# Proiect-TSC_v16.net
KiCad netlist of a schematic drawn in EAGLE
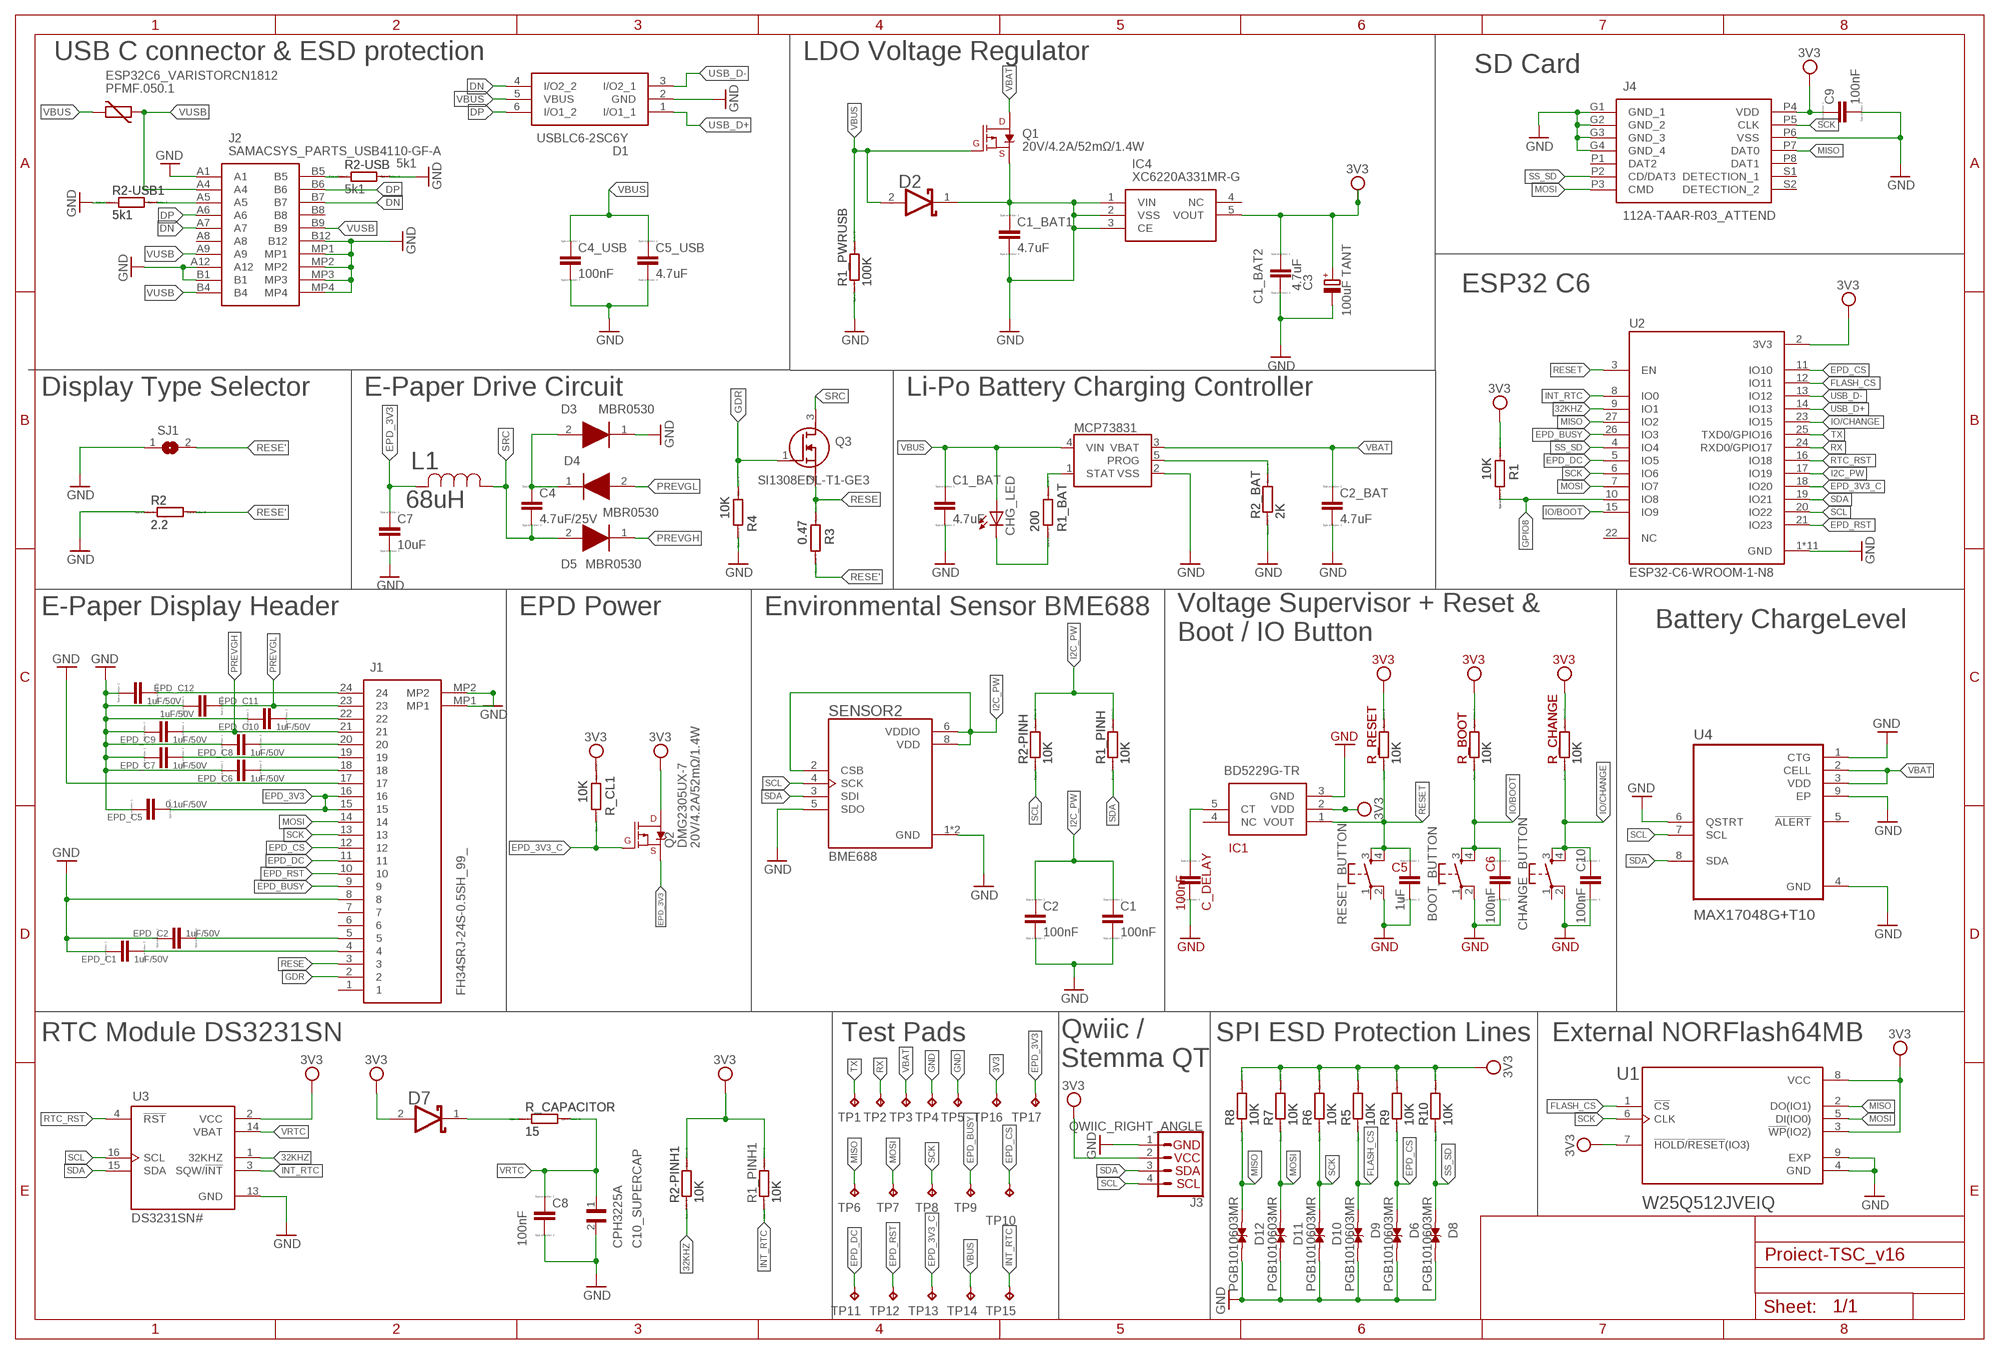
[diagram p0: schematic, sheet 1]

(export (version "E")
  (design (tool "Eeschema 10.0.6"))
  (components
    (comp (ref "BOOT_BUTTON")
      (value "BUTTON_CUSYOMV1")
      (footprint "eagle-import:MYBUTTON")
      (libsource (lib "eagle-import") (part "BUTTON_CUSYOMV1"))
    )
    (comp (ref "C1")
      (value "100nF")
      (footprint "eagle-import:EAGLE-LTSPICE_C0402")
      (libsource (lib "eagle-import") (part "EAGLE-LTSPICE_CC0402"))
    )
    (comp (ref "C1_BAT")
      (value "4.7uF")
      (footprint "eagle-import:EAGLE-LTSPICE_C0402")
      (libsource (lib "eagle-import") (part "EAGLE-LTSPICE_CC0402"))
    )
    (comp (ref "C1_BAT1")
      (value "4.7uF")
      (footprint "eagle-import:EAGLE-LTSPICE_C0402")
      (libsource (lib "eagle-import") (part "EAGLE-LTSPICE_CC0402"))
    )
    (comp (ref "C1_BAT2")
      (value "4.7uF")
      (footprint "eagle-import:EAGLE-LTSPICE_C0402")
      (libsource (lib "eagle-import") (part "EAGLE-LTSPICE_CC0402"))
    )
    (comp (ref "C2")
      (value "100nF")
      (footprint "eagle-import:EAGLE-LTSPICE_C0402")
      (libsource (lib "eagle-import") (part "EAGLE-LTSPICE_CC0402"))
    )
    (comp (ref "C2_BAT")
      (value "4.7uF")
      (footprint "eagle-import:EAGLE-LTSPICE_C0402")
      (libsource (lib "eagle-import") (part "EAGLE-LTSPICE_CC0402"))
    )
    (comp (ref "C3")
      (value "100uF TANT")
      (footprint "eagle-import:RCL_CT3528")
      (libsource (lib "eagle-import") (part "RCL_CPOL-EUCT3528"))
    )
    (comp (ref "C4")
      (value "4.7uF/25V")
      (footprint "eagle-import:EAGLE-LTSPICE_C0402")
      (libsource (lib "eagle-import") (part "EAGLE-LTSPICE_CC0402"))
    )
    (comp (ref "C4_USB")
      (value "100nF")
      (footprint "eagle-import:EAGLE-LTSPICE_C0402")
      (libsource (lib "eagle-import") (part "EAGLE-LTSPICE_CC0402"))
    )
    (comp (ref "C5")
      (value "1uF")
      (footprint "eagle-import:EAGLE-LTSPICE_C0402")
      (libsource (lib "eagle-import") (part "EAGLE-LTSPICE_CC0402"))
    )
    (comp (ref "C5_USB")
      (value "4.7uF")
      (footprint "eagle-import:EAGLE-LTSPICE_C0402")
      (libsource (lib "eagle-import") (part "EAGLE-LTSPICE_CC0402"))
    )
    (comp (ref "C6")
      (value "100nF")
      (footprint "eagle-import:EAGLE-LTSPICE_C0402")
      (libsource (lib "eagle-import") (part "EAGLE-LTSPICE_CC0402"))
    )
    (comp (ref "C7")
      (value "10uF")
      (footprint "eagle-import:EAGLE-LTSPICE_C0402")
      (libsource (lib "eagle-import") (part "EAGLE-LTSPICE_CC0402"))
    )
    (comp (ref "C8")
      (value "100nF")
      (footprint "eagle-import:EAGLE-LTSPICE_C0402")
      (libsource (lib "eagle-import") (part "EAGLE-LTSPICE_CC0402"))
    )
    (comp (ref "C9")
      (value "100nF")
      (footprint "eagle-import:EAGLE-LTSPICE_C0402")
      (libsource (lib "eagle-import") (part "EAGLE-LTSPICE_CC0402"))
    )
    (comp (ref "C10")
      (value "100nF")
      (footprint "eagle-import:EAGLE-LTSPICE_C0402")
      (libsource (lib "eagle-import") (part "EAGLE-LTSPICE_CC0402"))
    )
    (comp (ref "C10_SUPERCAP")
      (value "CPH3225A")
      (footprint "eagle-import:CAPCP3225X100N")
      (fields (field (name "MF") "Seiko Instruments"))
      (libsource (lib "eagle-import") (part "CPH3225A"))
    )
    (comp (ref "CHANGE_BUTTON")
      (value "BUTTON_CUSYOMV1")
      (footprint "eagle-import:MYBUTTON")
      (libsource (lib "eagle-import") (part "BUTTON_CUSYOMV1"))
    )
    (comp (ref "CHG_LED")
      (value "1")
      (footprint "eagle-import:ADAFRUIT_CHIP-LED0603")
      (libsource (lib "eagle-import") (part "ADAFRUIT_LEDCHIP-LED0603"))
    )
    (comp (ref "C_DELAY")
      (value "100nF")
      (footprint "eagle-import:EAGLE-LTSPICE_C0402")
      (libsource (lib "eagle-import") (part "EAGLE-LTSPICE_CC0402"))
    )
    (comp (ref "D1")
      (value "USBLC6-2SC6Y")
      (footprint "eagle-import:SOT95P280X145-6N")
      (fields (field (name "MF") "STMicroelectronics"))
      (libsource (lib "eagle-import") (part "USBLC6-2SC6Y"))
    )
    (comp (ref "D2")
      (value "ESP32_WROVER_AVX---SD0805S020S1R0_AVX_SD0805S020S1R0_0_0AVX_SD0805S020S1R0_0_0")
      (footprint "eagle-import:ESP32_WROVER_AVX---SD0805S020S1R0_AVX_SD0805S020S1R0_0")
      (fields
        (field (name "DIGIKEY_PART_NUMBER") "478-7800-1-ND")
        (field (name "MF") "AVX")
        (field (name "MOUSER_PART_NUMBER") "581-SD0805S020S1R0")
      )
      (libsource (lib "eagle-import") (part "ESP32_WROVER_AVX---SD0805S020S1R0_AVX_SD0805S020S1R0_0_0AVX_SD0805S020S1R0_0_0"))
    )
    (comp (ref "D3")
      (value "MBR0530")
      (footprint "eagle-import:SOD3716X135N")
      (fields (field (name "MF") "ON Semiconductor"))
      (libsource (lib "eagle-import") (part "MBR0530"))
    )
    (comp (ref "D4")
      (value "MBR0530")
      (footprint "eagle-import:SOD3716X135N")
      (fields (field (name "MF") "ON Semiconductor"))
      (libsource (lib "eagle-import") (part "MBR0530"))
    )
    (comp (ref "D5")
      (value "MBR0530")
      (footprint "eagle-import:SOD3716X135N")
      (fields (field (name "MF") "ON Semiconductor"))
      (libsource (lib "eagle-import") (part "MBR0530"))
    )
    (comp (ref "D6")
      (value "PGB1010603MR")
      (footprint "eagle-import:DIOC1608X36N")
      (fields (field (name "MF") "Littelfuse Inc."))
      (libsource (lib "eagle-import") (part "PGB1010603MR"))
    )
    (comp (ref "D7")
      (value "ESP32_WROVER_AVX---SD0805S020S1R0_AVX_SD0805S020S1R0_0_0AVX_SD0805S020S1R0_0_0")
      (footprint "eagle-import:ESP32_WROVER_AVX---SD0805S020S1R0_AVX_SD0805S020S1R0_0")
      (fields
        (field (name "DIGIKEY_PART_NUMBER") "478-7800-1-ND")
        (field (name "MF") "AVX")
        (field (name "MOUSER_PART_NUMBER") "581-SD0805S020S1R0")
      )
      (libsource (lib "eagle-import") (part "ESP32_WROVER_AVX---SD0805S020S1R0_AVX_SD0805S020S1R0_0_0AVX_SD0805S020S1R0_0_0"))
    )
    (comp (ref "D8")
      (value "PGB1010603MR")
      (footprint "eagle-import:DIOC1608X36N")
      (fields (field (name "MF") "Littelfuse Inc."))
      (libsource (lib "eagle-import") (part "PGB1010603MR"))
    )
    (comp (ref "D9")
      (value "PGB1010603MR")
      (footprint "eagle-import:DIOC1608X36N")
      (fields (field (name "MF") "Littelfuse Inc."))
      (libsource (lib "eagle-import") (part "PGB1010603MR"))
    )
    (comp (ref "D10")
      (value "PGB1010603MR")
      (footprint "eagle-import:DIOC1608X36N")
      (fields (field (name "MF") "Littelfuse Inc."))
      (libsource (lib "eagle-import") (part "PGB1010603MR"))
    )
    (comp (ref "D11")
      (value "PGB1010603MR")
      (footprint "eagle-import:DIOC1608X36N")
      (fields (field (name "MF") "Littelfuse Inc."))
      (libsource (lib "eagle-import") (part "PGB1010603MR"))
    )
    (comp (ref "D12")
      (value "PGB1010603MR")
      (footprint "eagle-import:DIOC1608X36N")
      (fields (field (name "MF") "Littelfuse Inc."))
      (libsource (lib "eagle-import") (part "PGB1010603MR"))
    )
    (comp (ref "EPD_C1")
      (value "1uF/50V")
      (footprint "eagle-import:EAGLE-LTSPICE_C0402")
      (libsource (lib "eagle-import") (part "EAGLE-LTSPICE_CC0402"))
    )
    (comp (ref "EPD_C2")
      (value "1uF/50V")
      (footprint "eagle-import:EAGLE-LTSPICE_C0402")
      (libsource (lib "eagle-import") (part "EAGLE-LTSPICE_CC0402"))
    )
    (comp (ref "EPD_C5")
      (value "0.1uF/50V")
      (footprint "eagle-import:EAGLE-LTSPICE_C0402")
      (libsource (lib "eagle-import") (part "EAGLE-LTSPICE_CC0402"))
    )
    (comp (ref "EPD_C6")
      (value "1uF/50V")
      (footprint "eagle-import:EAGLE-LTSPICE_C0402")
      (libsource (lib "eagle-import") (part "EAGLE-LTSPICE_CC0402"))
    )
    (comp (ref "EPD_C7")
      (value "1uF/50V")
      (footprint "eagle-import:EAGLE-LTSPICE_C0402")
      (libsource (lib "eagle-import") (part "EAGLE-LTSPICE_CC0402"))
    )
    (comp (ref "EPD_C8")
      (value "1uF/50V")
      (footprint "eagle-import:EAGLE-LTSPICE_C0402")
      (libsource (lib "eagle-import") (part "EAGLE-LTSPICE_CC0402"))
    )
    (comp (ref "EPD_C9")
      (value "1uF/50V")
      (footprint "eagle-import:EAGLE-LTSPICE_C0402")
      (libsource (lib "eagle-import") (part "EAGLE-LTSPICE_CC0402"))
    )
    (comp (ref "EPD_C10")
      (value "1uF/50V")
      (footprint "eagle-import:EAGLE-LTSPICE_C0402")
      (libsource (lib "eagle-import") (part "EAGLE-LTSPICE_CC0402"))
    )
    (comp (ref "EPD_C11")
      (value "1uF/50V")
      (footprint "eagle-import:EAGLE-LTSPICE_C0402")
      (libsource (lib "eagle-import") (part "EAGLE-LTSPICE_CC0402"))
    )
    (comp (ref "EPD_C12")
      (value "1uF/50V")
      (footprint "eagle-import:EAGLE-LTSPICE_C0402")
      (libsource (lib "eagle-import") (part "EAGLE-LTSPICE_CC0402"))
    )
    (comp (ref "IC1")
      (value "BD5229G-TR")
      (footprint "eagle-import:SOT95P280X125-5N")
      (fields (field (name "MOUSER_PART_NUMBER") "755-BD5229G-TR"))
      (libsource (lib "eagle-import") (part "BD5229G-TR"))
    )
    (comp (ref "IC4")
      (value "XC6220A331MR-G")
      (footprint "eagle-import:SOT95P280X120-5N")
      (fields (field (name "MOUSER_PART_NUMBER") "865-XC6220A331MR-G"))
      (libsource (lib "eagle-import") (part "XC6220A331MR-G"))
    )
    (comp (ref "J1")
      (value "FH34SRJ-24S-0.5SH_99_")
      (footprint "eagle-import:FH34SRJ24S05SH99")
      (fields
        (field (name "MANUFACTURER_PART_NUMBER") "FH34SRJ-24S-0.5SH(99)")
        (field (name "MOUSER_PART_NUMBER") "798-FH34SRJ24S05SH99")
      )
      (libsource (lib "eagle-import") (part "FH34SRJ-24S-0.5SH_99_"))
    )
    (comp (ref "J2")
      (value "SAMACSYS_PARTS_USB4110-GF-A")
      (footprint "eagle-import:SAMACSYS_PARTS_USB4110GFA")
      (fields
        (field (name "MANUFACTURER_PART_NUMBER") "USB4110-GF-A")
        (field (name "MOUSER_PART_NUMBER") "640-USB4110-GF-A")
      )
      (libsource (lib "eagle-import") (part "SAMACSYS_PARTS_USB4110-GF-A"))
    )
    (comp (ref "J3")
      (value "QWIIC_RIGHT_ANGLE")
      (footprint "eagle-import:JST04_1MM_RA")
      (libsource (lib "eagle-import") (part "QWIIC_CONNECTORJS-1MM"))
    )
    (comp (ref "J4")
      (value "112A-TAAR-R03_ATTEND")
      (footprint "eagle-import:112ATAARR03ATTEND")
      (fields (field (name "MANUFACTURER_PART_NUMBER") "112A-TAAR-R03 ATTEND"))
      (libsource (lib "eagle-import") (part "112A-TAAR-R03_ATTEND"))
    )
    (comp (ref "L1")
      (value "68uH")
      (footprint "eagle-import:IND_4828-WE-TPC_WRE")
      (fields
        (field (name "MANUFACTURER_PART_NUMBER") "744043680")
        (field (name "COPYRIGHT") "Copyright (C) 2024 Ultra Librarian. All rights reserved.")
      )
      (libsource (lib "eagle-import") (part "744043680IND_4828-WE-TPC_WRE"))
    )
    (comp (ref "MCP73831")
      (value "ESP32_WROVER_SPARKFUN-IC-POWER_MCP73831")
      (footprint "eagle-import:ESP32_WROVER_SPARKFUN-IC-POWER_SOT23-5")
      (libsource (lib "eagle-import") (part "ESP32_WROVER_SPARKFUN-IC-POWER_MCP73831"))
    )
    (comp (ref "PFMF.050.1")
      (value "ESP32C6_VARISTORCN1812")
      (footprint "eagle-import:ESP32C6_VARISTOR_CT_CN1812")
      (libsource (lib "eagle-import") (part "ESP32C6_VARISTORCN1812"))
    )
    (comp (ref "Q1")
      (value "20V/4.2A/52mΩ/1.4W")
      (footprint "eagle-import:ESP32_WROVER_SPARKFUN-DISCRETESEMI_SOT23-3")
      (libsource (lib "eagle-import") (part "ESP32_WROVER_SPARKFUN-DISCRETESEMI_MOSFET_PCH-DMG2305UX-7"))
    )
    (comp (ref "Q2")
      (value "20V/4.2A/52mΩ/1.4W")
      (footprint "eagle-import:ESP32_WROVER_SPARKFUN-DISCRETESEMI_SOT23-3")
      (libsource (lib "eagle-import") (part "ESP32_WROVER_SPARKFUN-DISCRETESEMI_MOSFET_PCH-DMG2305UX-7"))
    )
    (comp (ref "Q3")
      (value "SI1308EDL-T1-GE3")
      (footprint "eagle-import:SOT65P210X110-3N")
      (fields (field (name "MF") "Vishay Siliconix"))
      (libsource (lib "eagle-import") (part "SI1308EDL-T1-GE3"))
    )
    (comp (ref "R1")
      (value "10K")
      (footprint "eagle-import:ESP32_WROVER_EAGLE-LTSPICE_R0402")
      (libsource (lib "eagle-import") (part "ESP32_WROVER_EAGLE-LTSPICE_RR0402"))
    )
    (comp (ref "R1_BAT")
      (value "200")
      (footprint "eagle-import:ESP32_WROVER_EAGLE-LTSPICE_R0402")
      (libsource (lib "eagle-import") (part "ESP32_WROVER_EAGLE-LTSPICE_RR0402"))
    )
    (comp (ref "R1_PINH")
      (value "10K")
      (footprint "eagle-import:ESP32_WROVER_EAGLE-LTSPICE_R0402")
      (libsource (lib "eagle-import") (part "ESP32_WROVER_EAGLE-LTSPICE_RR0402"))
    )
    (comp (ref "R1_PINH1")
      (value "10K")
      (footprint "eagle-import:ESP32_WROVER_EAGLE-LTSPICE_R0402")
      (libsource (lib "eagle-import") (part "ESP32_WROVER_EAGLE-LTSPICE_RR0402"))
    )
    (comp (ref "R1_PWRUSB")
      (value "100K")
      (footprint "eagle-import:ESP32_WROVER_EAGLE-LTSPICE_R0402")
      (libsource (lib "eagle-import") (part "ESP32_WROVER_EAGLE-LTSPICE_RR0402"))
    )
    (comp (ref "R2")
      (value "2.2")
      (footprint "eagle-import:ESP32_WROVER_EAGLE-LTSPICE_R0402")
      (libsource (lib "eagle-import") (part "ESP32_WROVER_EAGLE-LTSPICE_RR0402"))
    )
    (comp (ref "R2-PINH")
      (value "10K")
      (footprint "eagle-import:ESP32_WROVER_EAGLE-LTSPICE_R0402")
      (libsource (lib "eagle-import") (part "ESP32_WROVER_EAGLE-LTSPICE_RR0402"))
    )
    (comp (ref "R2-PINH1")
      (value "10K")
      (footprint "eagle-import:ESP32_WROVER_EAGLE-LTSPICE_R0402")
      (libsource (lib "eagle-import") (part "ESP32_WROVER_EAGLE-LTSPICE_RR0402"))
    )
    (comp (ref "R2-USB")
      (value "5k1")
      (footprint "eagle-import:ESP32_WROVER_EAGLE-LTSPICE_R0402")
      (libsource (lib "eagle-import") (part "ESP32_WROVER_EAGLE-LTSPICE_RR0402"))
    )
    (comp (ref "R2-USB1")
      (value "5k1")
      (footprint "eagle-import:ESP32_WROVER_EAGLE-LTSPICE_R0402")
      (libsource (lib "eagle-import") (part "ESP32_WROVER_EAGLE-LTSPICE_RR0402"))
    )
    (comp (ref "R2_BAT")
      (value "2K")
      (footprint "eagle-import:ESP32_WROVER_EAGLE-LTSPICE_R0402")
      (libsource (lib "eagle-import") (part "ESP32_WROVER_EAGLE-LTSPICE_RR0402"))
    )
    (comp (ref "R3")
      (value "0.47")
      (footprint "eagle-import:ESP32_WROVER_EAGLE-LTSPICE_R0402")
      (libsource (lib "eagle-import") (part "ESP32_WROVER_EAGLE-LTSPICE_RR0402"))
    )
    (comp (ref "R4")
      (value "10K")
      (footprint "eagle-import:ESP32_WROVER_EAGLE-LTSPICE_R0402")
      (libsource (lib "eagle-import") (part "ESP32_WROVER_EAGLE-LTSPICE_RR0402"))
    )
    (comp (ref "R5")
      (value "10K")
      (footprint "eagle-import:ESP32_WROVER_EAGLE-LTSPICE_R0402")
      (libsource (lib "eagle-import") (part "ESP32_WROVER_EAGLE-LTSPICE_RR0402"))
    )
    (comp (ref "R6")
      (value "10K")
      (footprint "eagle-import:ESP32_WROVER_EAGLE-LTSPICE_R0402")
      (libsource (lib "eagle-import") (part "ESP32_WROVER_EAGLE-LTSPICE_RR0402"))
    )
    (comp (ref "R7")
      (value "10K")
      (footprint "eagle-import:ESP32_WROVER_EAGLE-LTSPICE_R0402")
      (libsource (lib "eagle-import") (part "ESP32_WROVER_EAGLE-LTSPICE_RR0402"))
    )
    (comp (ref "R8")
      (value "10K")
      (footprint "eagle-import:ESP32_WROVER_EAGLE-LTSPICE_R0402")
      (libsource (lib "eagle-import") (part "ESP32_WROVER_EAGLE-LTSPICE_RR0402"))
    )
    (comp (ref "R9")
      (value "10K")
      (footprint "eagle-import:ESP32_WROVER_EAGLE-LTSPICE_R0402")
      (libsource (lib "eagle-import") (part "ESP32_WROVER_EAGLE-LTSPICE_RR0402"))
    )
    (comp (ref "R10")
      (value "10K")
      (footprint "eagle-import:ESP32_WROVER_EAGLE-LTSPICE_R0402")
      (libsource (lib "eagle-import") (part "ESP32_WROVER_EAGLE-LTSPICE_RR0402"))
    )
    (comp (ref "RESET_BUTTON")
      (value "BUTTON_CUSYOMV1")
      (footprint "eagle-import:MYBUTTON")
      (libsource (lib "eagle-import") (part "BUTTON_CUSYOMV1"))
    )
    (comp (ref "R_BOOT")
      (value "10K")
      (footprint "eagle-import:ESP32_WROVER_EAGLE-LTSPICE_R0402")
      (libsource (lib "eagle-import") (part "ESP32_WROVER_EAGLE-LTSPICE_RR0402"))
    )
    (comp (ref "R_CAPACITOR")
      (value "15")
      (footprint "eagle-import:ESP32_WROVER_EAGLE-LTSPICE_R0402")
      (libsource (lib "eagle-import") (part "ESP32_WROVER_EAGLE-LTSPICE_RR0402"))
    )
    (comp (ref "R_CHANGE")
      (value "10K")
      (footprint "eagle-import:ESP32_WROVER_EAGLE-LTSPICE_R0402")
      (libsource (lib "eagle-import") (part "ESP32_WROVER_EAGLE-LTSPICE_RR0402"))
    )
    (comp (ref "R_CL1")
      (value "10K")
      (footprint "eagle-import:ESP32_WROVER_EAGLE-LTSPICE_R0402")
      (libsource (lib "eagle-import") (part "ESP32_WROVER_EAGLE-LTSPICE_RR0402"))
    )
    (comp (ref "R_RESET")
      (value "10K")
      (footprint "eagle-import:ESP32_WROVER_EAGLE-LTSPICE_R0402")
      (libsource (lib "eagle-import") (part "ESP32_WROVER_EAGLE-LTSPICE_RR0402"))
    )
    (comp (ref "SENSOR2")
      (value "ESP32_WROVER_BME680_BME680")
      (footprint "eagle-import:ESP32_WROVER_BME680_PSON80P300X300X100-8N")
      (fields (field (name "MF") "Bosch Sensortec") (field (name "MP") "BME680"))
      (libsource (lib "eagle-import") (part "ESP32_WROVER_BME680_BME680"))
    )
    (comp (ref "SJ1") (value "1") (footprint "eagle-import:SJ") (libsource (lib "eagle-import") (part "SJ")))
    (comp (ref "TP1")
      (value "TPTP20R")
      (footprint "eagle-import:TP20R")
      (libsource (lib "eagle-import") (part "TPTP20R"))
    )
    (comp (ref "TP2")
      (value "TPTP20R")
      (footprint "eagle-import:TP20R")
      (libsource (lib "eagle-import") (part "TPTP20R"))
    )
    (comp (ref "TP3")
      (value "TPTP20R")
      (footprint "eagle-import:TP20R")
      (libsource (lib "eagle-import") (part "TPTP20R"))
    )
    (comp (ref "TP4")
      (value "TPTP20R")
      (footprint "eagle-import:TP20R")
      (libsource (lib "eagle-import") (part "TPTP20R"))
    )
    (comp (ref "TP5")
      (value "TPTP20R")
      (footprint "eagle-import:TP20R")
      (libsource (lib "eagle-import") (part "TPTP20R"))
    )
    (comp (ref "TP6")
      (value "TPTP20R")
      (footprint "eagle-import:TP20R")
      (libsource (lib "eagle-import") (part "TPTP20R"))
    )
    (comp (ref "TP7")
      (value "TPTP20R")
      (footprint "eagle-import:TP20R")
      (libsource (lib "eagle-import") (part "TPTP20R"))
    )
    (comp (ref "TP8")
      (value "TPTP20R")
      (footprint "eagle-import:TP20R")
      (libsource (lib "eagle-import") (part "TPTP20R"))
    )
    (comp (ref "TP9")
      (value "TPTP20R")
      (footprint "eagle-import:TP20R")
      (libsource (lib "eagle-import") (part "TPTP20R"))
    )
    (comp (ref "TP10")
      (value "TPTP20R")
      (footprint "eagle-import:TP20R")
      (libsource (lib "eagle-import") (part "TPTP20R"))
    )
    (comp (ref "TP11")
      (value "TPTP20R")
      (footprint "eagle-import:TP20R")
      (libsource (lib "eagle-import") (part "TPTP20R"))
    )
    (comp (ref "TP12")
      (value "TPTP20R")
      (footprint "eagle-import:TP20R")
      (libsource (lib "eagle-import") (part "TPTP20R"))
    )
    (comp (ref "TP13")
      (value "TPTP20R")
      (footprint "eagle-import:TP20R")
      (libsource (lib "eagle-import") (part "TPTP20R"))
    )
    (comp (ref "TP14")
      (value "TPTP20R")
      (footprint "eagle-import:TP20R")
      (libsource (lib "eagle-import") (part "TPTP20R"))
    )
    (comp (ref "TP15")
      (value "TPTP20R")
      (footprint "eagle-import:TP20R")
      (libsource (lib "eagle-import") (part "TPTP20R"))
    )
    (comp (ref "TP16")
      (value "TPTP20R")
      (footprint "eagle-import:TP20R")
      (libsource (lib "eagle-import") (part "TPTP20R"))
    )
    (comp (ref "TP17")
      (value "TPTP20R")
      (footprint "eagle-import:TP20R")
      (libsource (lib "eagle-import") (part "TPTP20R"))
    )
    (comp (ref "U1")
      (value "W25Q512JVEIQ")
      (footprint "eagle-import:SON127P600X800X80-9N")
      (fields (field (name "MF") "Winbond Electronics"))
      (libsource (lib "eagle-import") (part "W25Q512JVEIQ"))
    )
    (comp (ref "U2")
      (value "ESP32-C6-WROOM-1-N8")
      (footprint "eagle-import:XCVR_ESP32-C6-WROOM-1-N8")
      (fields (field (name "MF") "Espressif Systems"))
      (libsource (lib "eagle-import") (part "ESP32-C6-WROOM-1-N8"))
    )
    (comp (ref "U3")
      (value "DS3231SN#")
      (footprint "eagle-import:SOIC127P1032X265-16N")
      (fields (field (name "MF") "Analog Devices"))
      (libsource (lib "eagle-import") (part "DS3231SN#"))
    )
    (comp (ref "U4")
      (value "MAX17048G+T10")
      (footprint "eagle-import:SON50P200X200X80-9N")
      (fields (field (name "MF") "Analog Devices"))
      (libsource (lib "eagle-import") (part "MAX17048G+T10"))
    )
  )
  (nets
    (net (code "1") (name "3V3") (class "Default")
      (node (ref "C1_BAT2") (pin "1") (pinfunction "1_1") (pintype "passive"))
      (node (ref "C3") (pin "+") (pinfunction "+_+") (pintype "passive"))
      (node (ref "C9") (pin "1") (pinfunction "1_1") (pintype "passive"))
      (node (ref "D7") (pin "2") (pinfunction "ANODE_2") (pintype "bidirectional"))
      (node (ref "IC1") (pin "2") (pinfunction "VDD_2") (pintype "bidirectional"))
      (node (ref "IC4") (pin "5") (pinfunction "VOUT_5") (pintype "bidirectional"))
      (node (ref "J3") (pin "2") (pinfunction "2_2") (pintype "power_in"))
      (node (ref "J4") (pin "P4") (pinfunction "VDD_P4") (pintype "bidirectional"))
      (node (ref "Q2") (pin "3") (pinfunction "D_3") (pintype "bidirectional"))
      (node (ref "R1") (pin "2") (pinfunction "2_2") (pintype "passive"))
      (node (ref "R10") (pin "2") (pinfunction "2_2") (pintype "passive"))
      (node (ref "R1_PINH1") (pin "2") (pinfunction "2_2") (pintype "passive"))
      (node (ref "R2-PINH1") (pin "2") (pinfunction "2_2") (pintype "passive"))
      (node (ref "R5") (pin "2") (pinfunction "2_2") (pintype "passive"))
      (node (ref "R6") (pin "2") (pinfunction "2_2") (pintype "passive"))
      (node (ref "R7") (pin "2") (pinfunction "2_2") (pintype "passive"))
      (node (ref "R8") (pin "2") (pinfunction "2_2") (pintype "passive"))
      (node (ref "R9") (pin "2") (pinfunction "2_2") (pintype "passive"))
      (node (ref "R_BOOT") (pin "2") (pinfunction "2_2") (pintype "passive"))
      (node (ref "R_CHANGE") (pin "2") (pinfunction "2_2") (pintype "passive"))
      (node (ref "R_CL1") (pin "2") (pinfunction "2_2") (pintype "passive"))
      (node (ref "R_RESET") (pin "2") (pinfunction "2_2") (pintype "passive"))
      (node (ref "TP16") (pin "TP") (pinfunction "TP_TP") (pintype "input"))
      (node (ref "U1") (pin "3") (pinfunction "~{WP}(IO2)_3") (pintype "bidirectional"))
      (node (ref "U1") (pin "7") (pinfunction "~{HOLD}/~{RESET}(IO3)_7") (pintype "bidirectional"))
      (node (ref "U1") (pin "8") (pinfunction "VCC_8") (pintype "power_in"))
      (node (ref "U2") (pin "2") (pinfunction "3V3_2") (pintype "power_in"))
      (node (ref "U3") (pin "2") (pinfunction "VCC_2") (pintype "power_in"))
    )
    (net (code "2") (name "32KHZ") (class "Default")
      (node (ref "R2-PINH1") (pin "1") (pinfunction "1_1") (pintype "passive"))
      (node (ref "U2") (pin "9") (pinfunction "IO1_9") (pintype "bidirectional"))
      (node (ref "U3") (pin "1") (pinfunction "32KHZ_1") (pintype "output"))
    )
    (net (code "3") (name "DN") (class "Default")
      (node (ref "D1") (pin "4") (pinfunction "I/O2_2_4") (pintype "bidirectional"))
      (node (ref "J2") (pin "A7") (pinfunction "A7_A7") (pintype "bidirectional"))
      (node (ref "J2") (pin "B7") (pinfunction "B7_B7") (pintype "bidirectional"))
    )
    (net (code "4") (name "DP") (class "Default")
      (node (ref "D1") (pin "6") (pinfunction "I/O1_2_6") (pintype "bidirectional"))
      (node (ref "J2") (pin "A6") (pinfunction "A6_A6") (pintype "bidirectional"))
      (node (ref "J2") (pin "B6") (pinfunction "B6_B6") (pintype "bidirectional"))
    )
    (net (code "5") (name "EPD_3V3") (class "Default")
      (node (ref "C7") (pin "1") (pinfunction "1_1") (pintype "passive"))
      (node (ref "EPD_C5") (pin "2") (pinfunction "2_2") (pintype "passive"))
      (node (ref "J1") (pin "15") (pinfunction "15_15") (pintype "bidirectional"))
      (node (ref "J1") (pin "16") (pinfunction "16_16") (pintype "bidirectional"))
      (node (ref "L1") (pin "2") (pinfunction "2_2") (pintype "passive"))
      (node (ref "Q2") (pin "2") (pinfunction "S_2") (pintype "bidirectional"))
      (node (ref "TP17") (pin "TP") (pinfunction "TP_TP") (pintype "input"))
    )
    (net (code "6") (name "EPD_3V3_C") (class "Default")
      (node (ref "Q2") (pin "1") (pinfunction "G_1") (pintype "bidirectional"))
      (node (ref "R_CL1") (pin "1") (pinfunction "1_1") (pintype "passive"))
      (node (ref "TP13") (pin "TP") (pinfunction "TP_TP") (pintype "input"))
      (node (ref "U2") (pin "18") (pinfunction "IO20_18") (pintype "bidirectional"))
    )
    (net (code "7") (name "EPD_BUSY") (class "Default")
      (node (ref "J1") (pin "9") (pinfunction "9_9") (pintype "bidirectional"))
      (node (ref "TP9") (pin "TP") (pinfunction "TP_TP") (pintype "input"))
      (node (ref "U2") (pin "26") (pinfunction "IO3_26") (pintype "bidirectional"))
    )
    (net (code "8") (name "EPD_CS") (class "Default")
      (node (ref "D6") (pin "1") (pinfunction "1_1") (pintype "passive"))
      (node (ref "J1") (pin "12") (pinfunction "12_12") (pintype "bidirectional"))
      (node (ref "R9") (pin "1") (pinfunction "1_1") (pintype "passive"))
      (node (ref "TP10") (pin "TP") (pinfunction "TP_TP") (pintype "input"))
      (node (ref "U2") (pin "11") (pinfunction "IO10_11") (pintype "bidirectional"))
    )
    (net (code "9") (name "EPD_DC") (class "Default")
      (node (ref "J1") (pin "11") (pinfunction "11_11") (pintype "bidirectional"))
      (node (ref "TP11") (pin "TP") (pinfunction "TP_TP") (pintype "input"))
      (node (ref "U2") (pin "5") (pinfunction "IO5_5") (pintype "bidirectional"))
    )
    (net (code "10") (name "EPD_RST") (class "Default")
      (node (ref "J1") (pin "10") (pinfunction "10_10") (pintype "bidirectional"))
      (node (ref "TP12") (pin "TP") (pinfunction "TP_TP") (pintype "input"))
      (node (ref "U2") (pin "21") (pinfunction "IO23_21") (pintype "bidirectional"))
    )
    (net (code "11") (name "FLASH_CS") (class "Default")
      (node (ref "D9") (pin "1") (pinfunction "1_1") (pintype "passive"))
      (node (ref "R5") (pin "1") (pinfunction "1_1") (pintype "passive"))
      (node (ref "U1") (pin "1") (pinfunction "~{CS}_1") (pintype "input"))
      (node (ref "U2") (pin "12") (pinfunction "IO11_12") (pintype "bidirectional"))
    )
    (net (code "12") (name "GDR") (class "Default")
      (node (ref "J1") (pin "2") (pinfunction "2_2") (pintype "bidirectional"))
      (node (ref "Q3") (pin "1") (pinfunction "G_1") (pintype "bidirectional"))
      (node (ref "R4") (pin "2") (pinfunction "2_2") (pintype "passive"))
    )
    (net (code "13") (name "GND") (class "Default")
      (node (ref "BOOT_BUTTON") (pin "2") (pinfunction "2_2") (pintype "passive"))
      (node (ref "C1") (pin "2") (pinfunction "2_2") (pintype "passive"))
      (node (ref "C10") (pin "2") (pinfunction "2_2") (pintype "passive"))
      (node (ref "C10_SUPERCAP") (pin "2") (pinfunction "2_2") (pintype "passive"))
      (node (ref "C1_BAT") (pin "2") (pinfunction "2_2") (pintype "passive"))
      (node (ref "C1_BAT1") (pin "1") (pinfunction "1_1") (pintype "passive"))
      (node (ref "C1_BAT1") (pin "2") (pinfunction "2_2") (pintype "passive"))
      (node (ref "C1_BAT2") (pin "2") (pinfunction "2_2") (pintype "passive"))
      (node (ref "C2") (pin "2") (pinfunction "2_2") (pintype "passive"))
      (node (ref "C2_BAT") (pin "2") (pinfunction "2_2") (pintype "passive"))
      (node (ref "C3") (pin "-") (pinfunction "-_-") (pintype "passive"))
      (node (ref "C4_USB") (pin "2") (pinfunction "2_2") (pintype "passive"))
      (node (ref "C5") (pin "2") (pinfunction "2_2") (pintype "passive"))
      (node (ref "C5_USB") (pin "2") (pinfunction "2_2") (pintype "passive"))
      (node (ref "C6") (pin "2") (pinfunction "2_2") (pintype "passive"))
      (node (ref "C7") (pin "2") (pinfunction "2_2") (pintype "passive"))
      (node (ref "C8") (pin "2") (pinfunction "2_2") (pintype "passive"))
      (node (ref "C9") (pin "2") (pinfunction "2_2") (pintype "passive"))
      (node (ref "CHANGE_BUTTON") (pin "2") (pinfunction "2_2") (pintype "passive"))
      (node (ref "C_DELAY") (pin "2") (pinfunction "2_2") (pintype "passive"))
      (node (ref "D1") (pin "2") (pinfunction "GND_2") (pintype "bidirectional"))
      (node (ref "D10") (pin "2") (pinfunction "2_2") (pintype "passive"))
      (node (ref "D11") (pin "2") (pinfunction "2_2") (pintype "passive"))
      (node (ref "D12") (pin "2") (pinfunction "2_2") (pintype "passive"))
      (node (ref "D2") (pin "1") (pinfunction "CATHODE_1") (pintype "bidirectional"))
      (node (ref "D3") (pin "1") (pinfunction "K_1") (pintype "bidirectional"))
      (node (ref "D6") (pin "2") (pinfunction "2_2") (pintype "passive"))
      (node (ref "D8") (pin "2") (pinfunction "2_2") (pintype "passive"))
      (node (ref "D9") (pin "2") (pinfunction "2_2") (pintype "passive"))
      (node (ref "EPD_C1") (pin "1") (pinfunction "1_1") (pintype "passive"))
      (node (ref "EPD_C10") (pin "1") (pinfunction "1_1") (pintype "passive"))
      (node (ref "EPD_C11") (pin "1") (pinfunction "1_1") (pintype "passive"))
      (node (ref "EPD_C12") (pin "1") (pinfunction "1_1") (pintype "passive"))
      (node (ref "EPD_C2") (pin "1") (pinfunction "1_1") (pintype "passive"))
      (node (ref "EPD_C5") (pin "1") (pinfunction "1_1") (pintype "passive"))
      (node (ref "EPD_C6") (pin "1") (pinfunction "1_1") (pintype "passive"))
      (node (ref "EPD_C7") (pin "1") (pinfunction "1_1") (pintype "passive"))
      (node (ref "EPD_C8") (pin "1") (pinfunction "1_1") (pintype "passive"))
      (node (ref "EPD_C9") (pin "1") (pinfunction "1_1") (pintype "passive"))
      (node (ref "IC1") (pin "3") (pinfunction "GND_3") (pintype "bidirectional"))
      (node (ref "IC4") (pin "1") (pinfunction "VIN_1") (pintype "bidirectional"))
      (node (ref "IC4") (pin "2") (pinfunction "VSS_2") (pintype "bidirectional"))
      (node (ref "IC4") (pin "3") (pinfunction "CE_3") (pintype "bidirectional"))
      (node (ref "J1") (pin "17") (pinfunction "17_17") (pintype "bidirectional"))
      (node (ref "J1") (pin "8") (pinfunction "8_8") (pintype "bidirectional"))
      (node (ref "J1") (pin "MP1") (pinfunction "MP1_MP1") (pintype "bidirectional"))
      (node (ref "J1") (pin "MP2") (pinfunction "MP2_MP2") (pintype "bidirectional"))
      (node (ref "J2") (pin "A1") (pinfunction "A1_A1") (pintype "bidirectional"))
      (node (ref "J2") (pin "A12") (pinfunction "A12_A12") (pintype "bidirectional"))
      (node (ref "J2") (pin "B1") (pinfunction "B1_B1") (pintype "bidirectional"))
      (node (ref "J2") (pin "B12") (pinfunction "B12_B12") (pintype "bidirectional"))
      (node (ref "J2") (pin "MP1") (pinfunction "MP1_MP1") (pintype "bidirectional"))
      (node (ref "J2") (pin "MP2") (pinfunction "MP2_MP2") (pintype "bidirectional"))
      (node (ref "J2") (pin "MP3") (pinfunction "MP3_MP3") (pintype "bidirectional"))
      (node (ref "J2") (pin "MP4") (pinfunction "MP4_MP4") (pintype "bidirectional"))
      (node (ref "J3") (pin "1") (pinfunction "1_1") (pintype "power_in"))
      (node (ref "J4") (pin "G1") (pinfunction "GND_1_G1") (pintype "bidirectional"))
      (node (ref "J4") (pin "G2") (pinfunction "GND_2_G2") (pintype "bidirectional"))
      (node (ref "J4") (pin "G3") (pinfunction "GND_3_G3") (pintype "bidirectional"))
      (node (ref "J4") (pin "G4") (pinfunction "GND_4_G4") (pintype "bidirectional"))
      (node (ref "J4") (pin "P6") (pinfunction "VSS_P6") (pintype "bidirectional"))
      (node (ref "MCP73831") (pin "2") (pinfunction "VSS_2") (pintype "power_in"))
      (node (ref "Q1") (pin "2") (pinfunction "S_2") (pintype "bidirectional"))
      (node (ref "R1_PWRUSB") (pin "1") (pinfunction "1_1") (pintype "passive"))
      (node (ref "R2") (pin "1") (pinfunction "1_1") (pintype "passive"))
      (node (ref "R2-USB") (pin "2") (pinfunction "2_2") (pintype "passive"))
      (node (ref "R2-USB1") (pin "1") (pinfunction "1_1") (pintype "passive"))
      (node (ref "R2_BAT") (pin "1") (pinfunction "1_1") (pintype "passive"))
      (node (ref "R4") (pin "1") (pinfunction "1_1") (pintype "passive"))
      (node (ref "RESET_BUTTON") (pin "2") (pinfunction "2_2") (pintype "passive"))
      (node (ref "SENSOR2") (pin "1") (pinfunction "GND_1") (pintype "power_in"))
      (node (ref "SENSOR2") (pin "5") (pinfunction "SDO_5") (pintype "bidirectional"))
      (node (ref "SENSOR2") (pin "7") (pinfunction "GND_7") (pintype "power_in"))
      (node (ref "SJ1") (pin "1") (pinfunction "1_1") (pintype "passive"))
      (node (ref "TP4") (pin "TP") (pinfunction "TP_TP") (pintype "input"))
      (node (ref "TP5") (pin "TP") (pinfunction "TP_TP") (pintype "input"))
      (node (ref "U1") (pin "4") (pinfunction "GND_4") (pintype "power_in"))
      (node (ref "U1") (pin "9") (pinfunction "EXP_9") (pintype "passive"))
      (node (ref "U2") (pin "1") (pinfunction "GND_1") (pintype "power_in"))
      (node (ref "U2") (pin "28") (pinfunction "GND_28") (pintype "power_in"))
      (node (ref "U2") (pin "29_1") (pinfunction "GND_29_1") (pintype "power_in"))
      (node (ref "U2") (pin "29_2") (pinfunction "GND_29_2") (pintype "power_in"))
      (node (ref "U2") (pin "29_3") (pinfunction "GND_29_3") (pintype "power_in"))
      (node (ref "U2") (pin "29_4") (pinfunction "GND_29_4") (pintype "power_in"))
      (node (ref "U2") (pin "29_5") (pinfunction "GND_29_5") (pintype "power_in"))
      (node (ref "U2") (pin "29_6") (pinfunction "GND_29_6") (pintype "power_in"))
      (node (ref "U2") (pin "29_7") (pinfunction "GND_29_7") (pintype "power_in"))
      (node (ref "U2") (pin "29_8") (pinfunction "GND_29_8") (pintype "power_in"))
      (node (ref "U2") (pin "29_9") (pinfunction "GND_29_9") (pintype "power_in"))
      (node (ref "U3") (pin "13") (pinfunction "GND_13") (pintype "power_in"))
      (node (ref "U4") (pin "1") (pinfunction "CTG_1") (pintype "power_in"))
      (node (ref "U4") (pin "4") (pinfunction "GND_4") (pintype "power_in"))
      (node (ref "U4") (pin "6") (pinfunction "QSTRT_6") (pintype "input"))
      (node (ref "U4") (pin "9") (pinfunction "EP_9") (pintype "power_in"))
    )
    (net (code "14") (name "GPIO8") (class "Default")
      (node (ref "R1") (pin "1") (pinfunction "1_1") (pintype "passive"))
      (node (ref "U2") (pin "10") (pinfunction "IO8_10") (pintype "bidirectional"))
    )
    (net (code "15") (name "I2C_PW") (class "Default")
      (node (ref "C1") (pin "1") (pinfunction "1_1") (pintype "passive"))
      (node (ref "C2") (pin "1") (pinfunction "1_1") (pintype "passive"))
      (node (ref "R1_PINH") (pin "2") (pinfunction "2_2") (pintype "passive"))
      (node (ref "R2-PINH") (pin "2") (pinfunction "2_2") (pintype "passive"))
      (node (ref "SENSOR2") (pin "2") (pinfunction "CSB_2") (pintype "input"))
      (node (ref "SENSOR2") (pin "6") (pinfunction "VDDIO_6") (pintype "power_in"))
      (node (ref "SENSOR2") (pin "8") (pinfunction "VDD_8") (pintype "power_in"))
      (node (ref "U2") (pin "17") (pinfunction "IO19_17") (pintype "bidirectional"))
    )
    (net (code "16") (name "INT_RTC") (class "Default")
      (node (ref "R1_PINH1") (pin "1") (pinfunction "1_1") (pintype "passive"))
      (node (ref "TP15") (pin "TP") (pinfunction "TP_TP") (pintype "input"))
      (node (ref "U2") (pin "8") (pinfunction "IO0_8") (pintype "bidirectional"))
      (node (ref "U3") (pin "3") (pinfunction "SQW/~{INT}_3") (pintype "output"))
    )
    (net (code "17") (name "IO{slash}BOOT") (class "Default")
      (node (ref "BOOT_BUTTON") (pin "3") (pinfunction "3_3") (pintype "passive"))
      (node (ref "BOOT_BUTTON") (pin "4") (pinfunction "4_4") (pintype "passive"))
      (node (ref "C6") (pin "1") (pinfunction "1_1") (pintype "passive"))
      (node (ref "R_BOOT") (pin "1") (pinfunction "1_1") (pintype "passive"))
      (node (ref "U2") (pin "15") (pinfunction "IO9_15") (pintype "bidirectional"))
    )
    (net (code "18") (name "IO{slash}CHANGE") (class "Default")
      (node (ref "C10") (pin "1") (pinfunction "1_1") (pintype "passive"))
      (node (ref "CHANGE_BUTTON") (pin "3") (pinfunction "3_3") (pintype "passive"))
      (node (ref "CHANGE_BUTTON") (pin "4") (pinfunction "4_4") (pintype "passive"))
      (node (ref "R_CHANGE") (pin "1") (pinfunction "1_1") (pintype "passive"))
      (node (ref "U2") (pin "23") (pinfunction "IO15_23") (pintype "bidirectional"))
    )
    (net (code "19") (name "MISO") (class "Default")
      (node (ref "D12") (pin "1") (pinfunction "1_1") (pintype "passive"))
      (node (ref "J4") (pin "P7") (pinfunction "DAT0_P7") (pintype "bidirectional"))
      (node (ref "R8") (pin "1") (pinfunction "1_1") (pintype "passive"))
      (node (ref "TP6") (pin "TP") (pinfunction "TP_TP") (pintype "input"))
      (node (ref "U1") (pin "2") (pinfunction "DO(IO1)_2") (pintype "bidirectional"))
      (node (ref "U2") (pin "27") (pinfunction "IO2_27") (pintype "bidirectional"))
    )
    (net (code "20") (name "MOSI") (class "Default")
      (node (ref "D11") (pin "1") (pinfunction "1_1") (pintype "passive"))
      (node (ref "J1") (pin "14") (pinfunction "14_14") (pintype "bidirectional"))
      (node (ref "J4") (pin "P3") (pinfunction "CMD_P3") (pintype "bidirectional"))
      (node (ref "R7") (pin "1") (pinfunction "1_1") (pintype "passive"))
      (node (ref "TP7") (pin "TP") (pinfunction "TP_TP") (pintype "input"))
      (node (ref "U1") (pin "5") (pinfunction "DI(IO0)_5") (pintype "bidirectional"))
      (node (ref "U2") (pin "7") (pinfunction "IO7_7") (pintype "bidirectional"))
    )
    (net (code "21") (name "Net-(CHG_LED-PadC)") (class "Default")
      (node (ref "CHG_LED") (pin "C") (pinfunction "C_C") (pintype "passive"))
      (node (ref "R1_BAT") (pin "1") (pinfunction "1_1") (pintype "passive"))
    )
    (net (code "22") (name "Net-(D3-A)") (class "Default")
      (node (ref "C4") (pin "1") (pinfunction "1_1") (pintype "passive"))
      (node (ref "D3") (pin "2") (pinfunction "A_2") (pintype "bidirectional"))
      (node (ref "D4") (pin "1") (pinfunction "K_1") (pintype "bidirectional"))
    )
    (net (code "23") (name "Net-(D7-CATHODE)") (class "Default")
      (node (ref "D7") (pin "1") (pinfunction "CATHODE_1") (pintype "bidirectional"))
      (node (ref "R_CAPACITOR") (pin "1") (pinfunction "1_1") (pintype "passive"))
    )
    (net (code "24") (name "Net-(EPD_C1-Pad2)") (class "Default")
      (node (ref "EPD_C1") (pin "2") (pinfunction "2_2") (pintype "passive"))
      (node (ref "J1") (pin "4") (pinfunction "4_4") (pintype "bidirectional"))
    )
    (net (code "25") (name "Net-(EPD_C2-Pad2)") (class "Default")
      (node (ref "EPD_C2") (pin "2") (pinfunction "2_2") (pintype "passive"))
      (node (ref "J1") (pin "5") (pinfunction "5_5") (pintype "bidirectional"))
    )
    (net (code "26") (name "Net-(EPD_C6-Pad2)") (class "Default")
      (node (ref "EPD_C6") (pin "2") (pinfunction "2_2") (pintype "passive"))
      (node (ref "J1") (pin "18") (pinfunction "18_18") (pintype "bidirectional"))
    )
    (net (code "27") (name "Net-(EPD_C7-Pad2)") (class "Default")
      (node (ref "EPD_C7") (pin "2") (pinfunction "2_2") (pintype "passive"))
      (node (ref "J1") (pin "19") (pinfunction "19_19") (pintype "bidirectional"))
    )
    (net (code "28") (name "Net-(EPD_C8-Pad2)") (class "Default")
      (node (ref "EPD_C8") (pin "2") (pinfunction "2_2") (pintype "passive"))
      (node (ref "J1") (pin "20") (pinfunction "20_20") (pintype "bidirectional"))
    )
    (net (code "29") (name "Net-(EPD_C10-Pad2)") (class "Default")
      (node (ref "EPD_C10") (pin "2") (pinfunction "2_2") (pintype "passive"))
      (node (ref "J1") (pin "22") (pinfunction "22_22") (pintype "bidirectional"))
    )
    (net (code "30") (name "Net-(EPD_C12-Pad2)") (class "Default")
      (node (ref "EPD_C12") (pin "2") (pinfunction "2_2") (pintype "passive"))
      (node (ref "J1") (pin "24") (pinfunction "24_24") (pintype "bidirectional"))
    )
    (net (code "31") (name "Net-(IC1-CT)") (class "Default")
      (node (ref "C_DELAY") (pin "1") (pinfunction "1_1") (pintype "passive"))
      (node (ref "IC1") (pin "5") (pinfunction "CT_5") (pintype "bidirectional"))
    )
    (net (code "32") (name "Net-(J2-PadA5)") (class "Default")
      (node (ref "J2") (pin "A5") (pinfunction "A5_A5") (pintype "bidirectional"))
      (node (ref "R2-USB1") (pin "2") (pinfunction "2_2") (pintype "passive"))
    )
    (net (code "33") (name "Net-(J2-PadB5)") (class "Default")
      (node (ref "J2") (pin "B5") (pinfunction "B5_B5") (pintype "bidirectional"))
      (node (ref "R2-USB") (pin "1") (pinfunction "1_1") (pintype "passive"))
    )
    (net (code "34") (name "Net-(MCP73831-PROG)") (class "Default")
      (node (ref "MCP73831") (pin "5") (pinfunction "PROG_5") (pintype "input"))
      (node (ref "R2_BAT") (pin "2") (pinfunction "2_2") (pintype "passive"))
    )
    (net (code "35") (name "Net-(MCP73831-STAT)") (class "Default")
      (node (ref "MCP73831") (pin "1") (pinfunction "STAT_1") (pintype "output"))
      (node (ref "R1_BAT") (pin "2") (pinfunction "2_2") (pintype "passive"))
    )
    (net (code "36") (name "PREVGH") (class "Default")
      (node (ref "D5") (pin "1") (pinfunction "K_1") (pintype "bidirectional"))
      (node (ref "EPD_C9") (pin "2") (pinfunction "2_2") (pintype "passive"))
      (node (ref "J1") (pin "21") (pinfunction "21_21") (pintype "bidirectional"))
    )
    (net (code "37") (name "PREVGL") (class "Default")
      (node (ref "D4") (pin "2") (pinfunction "A_2") (pintype "bidirectional"))
      (node (ref "EPD_C11") (pin "2") (pinfunction "2_2") (pintype "passive"))
      (node (ref "J1") (pin "23") (pinfunction "23_23") (pintype "bidirectional"))
    )
    (net (code "38") (name "RESE") (class "Default")
      (node (ref "J1") (pin "3") (pinfunction "3_3") (pintype "bidirectional"))
      (node (ref "Q3") (pin "2") (pinfunction "S_2") (pintype "bidirectional"))
      (node (ref "R3") (pin "2") (pinfunction "2_2") (pintype "passive"))
    )
    (net (code "39") (name "RESE'") (class "Default")
      (node (ref "R2") (pin "2") (pinfunction "2_2") (pintype "passive"))
      (node (ref "R3") (pin "1") (pinfunction "1_1") (pintype "passive"))
      (node (ref "SJ1") (pin "2") (pinfunction "2_2") (pintype "passive"))
    )
    (net (code "40") (name "RESET") (class "Default")
      (node (ref "C5") (pin "1") (pinfunction "1_1") (pintype "passive"))
      (node (ref "IC1") (pin "1") (pinfunction "VOUT_1") (pintype "bidirectional"))
      (node (ref "RESET_BUTTON") (pin "3") (pinfunction "3_3") (pintype "passive"))
      (node (ref "RESET_BUTTON") (pin "4") (pinfunction "4_4") (pintype "passive"))
      (node (ref "R_RESET") (pin "1") (pinfunction "1_1") (pintype "passive"))
      (node (ref "U2") (pin "3") (pinfunction "EN_3") (pintype "input"))
    )
    (net (code "41") (name "RTC_RST") (class "Default")
      (node (ref "U2") (pin "16") (pinfunction "IO18_16") (pintype "bidirectional"))
      (node (ref "U3") (pin "4") (pinfunction "~{RST}_4") (pintype "input"))
    )
    (net (code "42") (name "RX") (class "Default")
      (node (ref "TP2") (pin "TP") (pinfunction "TP_TP") (pintype "input"))
      (node (ref "U2") (pin "24") (pinfunction "RXD0/GPIO17_24") (pintype "bidirectional"))
    )
    (net (code "43") (name "SCK") (class "Default")
      (node (ref "D10") (pin "1") (pinfunction "1_1") (pintype "passive"))
      (node (ref "J1") (pin "13") (pinfunction "13_13") (pintype "bidirectional"))
      (node (ref "J4") (pin "P5") (pinfunction "CLK_P5") (pintype "bidirectional"))
      (node (ref "R6") (pin "1") (pinfunction "1_1") (pintype "passive"))
      (node (ref "TP8") (pin "TP") (pinfunction "TP_TP") (pintype "input"))
      (node (ref "U1") (pin "6") (pinfunction "CLK_6") (pintype "input"))
      (node (ref "U2") (pin "6") (pinfunction "IO6_6") (pintype "bidirectional"))
    )
    (net (code "44") (name "SCL") (class "Default")
      (node (ref "J3") (pin "4") (pinfunction "4_4") (pintype "passive"))
      (node (ref "R2-PINH") (pin "1") (pinfunction "1_1") (pintype "passive"))
      (node (ref "SENSOR2") (pin "4") (pinfunction "SCK_4") (pintype "input"))
      (node (ref "U2") (pin "20") (pinfunction "IO22_20") (pintype "bidirectional"))
      (node (ref "U3") (pin "16") (pinfunction "SCL_16") (pintype "input"))
      (node (ref "U4") (pin "7") (pinfunction "SCL_7") (pintype "input"))
    )
    (net (code "45") (name "SDA") (class "Default")
      (node (ref "J3") (pin "3") (pinfunction "3_3") (pintype "passive"))
      (node (ref "R1_PINH") (pin "1") (pinfunction "1_1") (pintype "passive"))
      (node (ref "SENSOR2") (pin "3") (pinfunction "SDI_3") (pintype "bidirectional"))
      (node (ref "U2") (pin "19") (pinfunction "IO21_19") (pintype "bidirectional"))
      (node (ref "U3") (pin "15") (pinfunction "SDA_15") (pintype "bidirectional"))
      (node (ref "U4") (pin "8") (pinfunction "SDA_8") (pintype "bidirectional"))
    )
    (net (code "46") (name "SRC") (class "Default")
      (node (ref "C4") (pin "2") (pinfunction "2_2") (pintype "passive"))
      (node (ref "D5") (pin "2") (pinfunction "A_2") (pintype "bidirectional"))
      (node (ref "L1") (pin "1") (pinfunction "1_1") (pintype "passive"))
      (node (ref "Q3") (pin "3") (pinfunction "D_3") (pintype "bidirectional"))
    )
    (net (code "47") (name "SS_SD") (class "Default")
      (node (ref "D8") (pin "1") (pinfunction "1_1") (pintype "passive"))
      (node (ref "J4") (pin "P2") (pinfunction "CD/DAT3_P2") (pintype "bidirectional"))
      (node (ref "R10") (pin "1") (pinfunction "1_1") (pintype "passive"))
      (node (ref "U2") (pin "4") (pinfunction "IO4_4") (pintype "bidirectional"))
    )
    (net (code "48") (name "TX") (class "Default")
      (node (ref "TP1") (pin "TP") (pinfunction "TP_TP") (pintype "input"))
      (node (ref "U2") (pin "25") (pinfunction "TXD0/GPIO16_25") (pintype "bidirectional"))
    )
    (net (code "49") (name "USB_D+") (class "Default")
      (node (ref "D1") (pin "1") (pinfunction "I/O1_1_1") (pintype "bidirectional"))
      (node (ref "U2") (pin "14") (pinfunction "IO13_14") (pintype "bidirectional"))
    )
    (net (code "50") (name "USB_D-") (class "Default")
      (node (ref "D1") (pin "3") (pinfunction "I/O2_1_3") (pintype "bidirectional"))
      (node (ref "U2") (pin "13") (pinfunction "IO12_13") (pintype "bidirectional"))
    )
    (net (code "51") (name "VBAT") (class "Default")
      (node (ref "C2_BAT") (pin "1") (pinfunction "1_1") (pintype "passive"))
      (node (ref "MCP73831") (pin "3") (pinfunction "VBAT_3") (pintype "power_in"))
      (node (ref "Q1") (pin "3") (pinfunction "D_3") (pintype "bidirectional"))
      (node (ref "TP3") (pin "TP") (pinfunction "TP_TP") (pintype "input"))
      (node (ref "U4") (pin "2") (pinfunction "CELL_2") (pintype "power_in"))
      (node (ref "U4") (pin "3") (pinfunction "VDD_3") (pintype "power_in"))
    )
    (net (code "52") (name "VBUS") (class "Default")
      (node (ref "C1_BAT") (pin "1") (pinfunction "1_1") (pintype "passive"))
      (node (ref "C4_USB") (pin "1") (pinfunction "1_1") (pintype "passive"))
      (node (ref "C5_USB") (pin "1") (pinfunction "1_1") (pintype "passive"))
      (node (ref "CHG_LED") (pin "A") (pinfunction "A_A") (pintype "passive"))
      (node (ref "D1") (pin "5") (pinfunction "VBUS_5") (pintype "bidirectional"))
      (node (ref "D2") (pin "2") (pinfunction "ANODE_2") (pintype "bidirectional"))
      (node (ref "MCP73831") (pin "4") (pinfunction "VIN_4") (pintype "power_in"))
      (node (ref "PFMF.050.1") (pin "2") (pinfunction "2_2") (pintype "passive"))
      (node (ref "Q1") (pin "1") (pinfunction "G_1") (pintype "bidirectional"))
      (node (ref "R1_PWRUSB") (pin "2") (pinfunction "2_2") (pintype "passive"))
      (node (ref "TP14") (pin "TP") (pinfunction "TP_TP") (pintype "input"))
    )
    (net (code "53") (name "VRTC") (class "Default")
      (node (ref "C10_SUPERCAP") (pin "1") (pinfunction "1_1") (pintype "passive"))
      (node (ref "C8") (pin "1") (pinfunction "1_1") (pintype "passive"))
      (node (ref "R_CAPACITOR") (pin "2") (pinfunction "2_2") (pintype "passive"))
      (node (ref "U3") (pin "14") (pinfunction "VBAT_14") (pintype "power_in"))
    )
    (net (code "54") (name "VUSB") (class "Default")
      (node (ref "J2") (pin "A4") (pinfunction "A4_A4") (pintype "bidirectional"))
      (node (ref "J2") (pin "A9") (pinfunction "A9_A9") (pintype "bidirectional"))
      (node (ref "J2") (pin "B4") (pinfunction "B4_B4") (pintype "bidirectional"))
      (node (ref "J2") (pin "B9") (pinfunction "B9_B9") (pintype "bidirectional"))
      (node (ref "PFMF.050.1") (pin "1") (pinfunction "1_1") (pintype "passive"))
    )
    (net (code "55") (name "unconnected-(BOOT_BUTTON-Pad1)") (class "Default")
      (node (ref "BOOT_BUTTON") (pin "1") (pinfunction "1_1") (pintype "passive"))
    )
    (net (code "56") (name "unconnected-(CHANGE_BUTTON-Pad1)") (class "Default")
      (node (ref "CHANGE_BUTTON") (pin "1") (pinfunction "1_1") (pintype "passive"))
    )
    (net (code "57") (name "unconnected-(IC1-NC-Pad4)") (class "Default")
      (node (ref "IC1") (pin "4") (pinfunction "NC_4") (pintype "no_connect"))
    )
    (net (code "58") (name "unconnected-(IC4-NC-Pad4)") (class "Default")
      (node (ref "IC4") (pin "4") (pinfunction "NC_4") (pintype "no_connect"))
    )
    (net (code "59") (name "unconnected-(J1-Pad1)") (class "Default")
      (node (ref "J1") (pin "1") (pinfunction "1_1") (pintype "bidirectional"))
    )
    (net (code "60") (name "unconnected-(J1-Pad6)") (class "Default")
      (node (ref "J1") (pin "6") (pinfunction "6_6") (pintype "bidirectional"))
    )
    (net (code "61") (name "unconnected-(J1-Pad7)") (class "Default")
      (node (ref "J1") (pin "7") (pinfunction "7_7") (pintype "bidirectional"))
    )
    (net (code "62") (name "unconnected-(J2-PadA8)") (class "Default")
      (node (ref "J2") (pin "A8") (pinfunction "A8_A8") (pintype "bidirectional"))
    )
    (net (code "63") (name "unconnected-(J2-PadB8)") (class "Default")
      (node (ref "J2") (pin "B8") (pinfunction "B8_B8") (pintype "bidirectional"))
    )
    (net (code "64") (name "unconnected-(J4-DAT1-PadP8)") (class "Default")
      (node (ref "J4") (pin "P8") (pinfunction "DAT1_P8") (pintype "bidirectional"))
    )
    (net (code "65") (name "unconnected-(J4-DAT2-PadP1)") (class "Default")
      (node (ref "J4") (pin "P1") (pinfunction "DAT2_P1") (pintype "bidirectional"))
    )
    (net (code "66") (name "unconnected-(J4-DETECTION_1-PadS1)") (class "Default")
      (node (ref "J4") (pin "S1") (pinfunction "DETECTION_1_S1") (pintype "bidirectional"))
    )
    (net (code "67") (name "unconnected-(J4-DETECTION_2-PadS2)") (class "Default")
      (node (ref "J4") (pin "S2") (pinfunction "DETECTION_2_S2") (pintype "bidirectional"))
    )
    (net (code "68") (name "unconnected-(RESET_BUTTON-Pad1)") (class "Default")
      (node (ref "RESET_BUTTON") (pin "1") (pinfunction "1_1") (pintype "passive"))
    )
    (net (code "69") (name "unconnected-(U2-NC-Pad22)") (class "Default")
      (node (ref "U2") (pin "22") (pinfunction "NC_22") (pintype "no_connect"))
    )
    (net (code "70") (name "unconnected-(U4-~{ALERT}-Pad5)") (class "Default")
      (node (ref "U4") (pin "5") (pinfunction "~{ALERT}_5") (pintype "output"))
    )
  )
)
